# LDM_SCH.net
KiCad netlist of a schematic drawn in Altium Designer
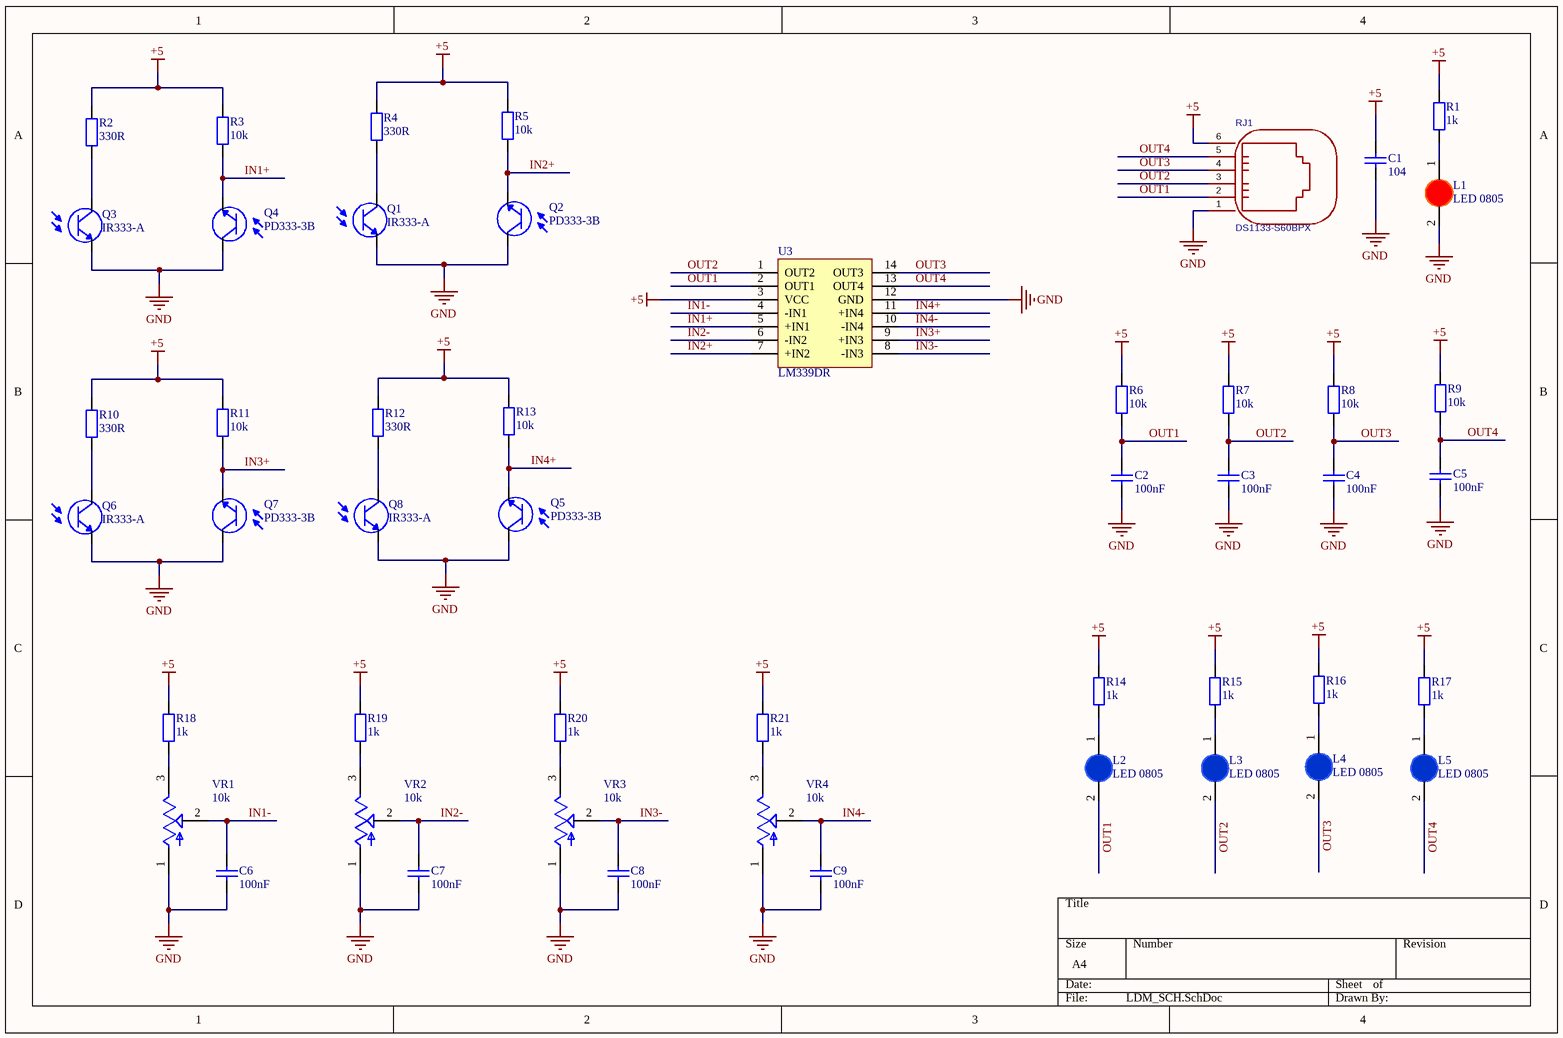
[diagram p0: LDM_SCH.SchDoc]

(export (version "E")
  (design (tool "Eeschema 10.0.6"))
  (components
    (comp (ref "C1")
      (value "104")
      (footprint "tu 0603")
      (description "Dán")
      (libsource (lib "namnt_Lib") (part "Tu 0603 104 50V 10%"))
    )
    (comp (ref "C2")
      (value "100nF")
      (footprint "tu 0603")
      (description "Dán")
      (libsource (lib "namnt_Lib") (part "Tu 0603 104 50V 10%"))
    )
    (comp (ref "C3")
      (value "100nF")
      (footprint "tu 0603")
      (description "Dán")
      (libsource (lib "namnt_Lib") (part "Tu 0603 104 50V 10%"))
    )
    (comp (ref "C4")
      (value "100nF")
      (footprint "tu 0603")
      (description "Dán")
      (libsource (lib "namnt_Lib") (part "Tu 0603 104 50V 10%"))
    )
    (comp (ref "C5")
      (value "100nF")
      (footprint "tu 0603")
      (description "Dán")
      (libsource (lib "namnt_Lib") (part "Tu 0603 104 50V 10%"))
    )
    (comp (ref "C6")
      (value "100nF")
      (footprint "tu 0603")
      (description "Dán")
      (libsource (lib "namnt_Lib") (part "Tu 0603 104 50V 10%"))
    )
    (comp (ref "C7")
      (value "100nF")
      (footprint "tu 0603")
      (description "Dán")
      (libsource (lib "namnt_Lib") (part "Tu 0603 104 50V 10%"))
    )
    (comp (ref "C8")
      (value "100nF")
      (footprint "tu 0603")
      (description "Dán")
      (libsource (lib "namnt_Lib") (part "Tu 0603 104 50V 10%"))
    )
    (comp (ref "C9")
      (value "100nF")
      (footprint "tu 0603")
      (description "Dán")
      (libsource (lib "namnt_Lib") (part "Tu 0603 104 50V 10%"))
    )
    (comp (ref "L1")
      (value "LED 0805")
      (footprint "LED-0805-Red")
      (description "Dán")
      (libsource (lib "namnt_Lib") (part "LED 0805 Do"))
    )
    (comp (ref "L2")
      (value "LED 0805")
      (footprint "LED-0805-Blue")
      (description "Dán")
      (libsource (lib "namnt_Lib") (part "LED 0805 Xanh Duong"))
    )
    (comp (ref "L3")
      (value "LED 0805")
      (footprint "LED-0805-Blue")
      (description "Dán")
      (libsource (lib "namnt_Lib") (part "LED 0805 Xanh Duong"))
    )
    (comp (ref "L4")
      (value "LED 0805")
      (footprint "LED-0805-Blue")
      (description "Dán")
      (libsource (lib "namnt_Lib") (part "LED 0805 Xanh Duong"))
    )
    (comp (ref "L5")
      (value "LED 0805")
      (footprint "LED-0805-Blue")
      (description "Dán")
      (libsource (lib "namnt_Lib") (part "LED 0805 Xanh Duong"))
    )
    (comp (ref "Q1")
      (value "IR333-A")
      (footprint "IR333-A")
      (fields (field (name "MP") "BPW16N"))
      (libsource (lib "namnt_Lib") (part "IR333-A"))
    )
    (comp (ref "Q2")
      (value "PD333-3B")
      (footprint "PD333-3B")
      (fields (field (name "MP") "BPW16N"))
      (libsource (lib "namnt_Lib") (part "PD333-3B"))
    )
    (comp (ref "Q3")
      (value "IR333-A")
      (footprint "IR333-A")
      (fields (field (name "MP") "BPW16N"))
      (libsource (lib "namnt_Lib") (part "IR333-A"))
    )
    (comp (ref "Q4")
      (value "PD333-3B")
      (footprint "PD333-3B")
      (fields (field (name "MP") "BPW16N"))
      (libsource (lib "namnt_Lib") (part "PD333-3B"))
    )
    (comp (ref "Q5")
      (value "PD333-3B")
      (footprint "PD333-3B")
      (fields (field (name "MP") "BPW16N"))
      (libsource (lib "namnt_Lib") (part "PD333-3B"))
    )
    (comp (ref "Q6")
      (value "IR333-A")
      (footprint "IR333-A")
      (fields (field (name "MP") "BPW16N"))
      (libsource (lib "namnt_Lib") (part "IR333-A"))
    )
    (comp (ref "Q7")
      (value "PD333-3B")
      (footprint "PD333-3B")
      (fields (field (name "MP") "BPW16N"))
      (libsource (lib "namnt_Lib") (part "PD333-3B"))
    )
    (comp (ref "Q8")
      (value "IR333-A")
      (footprint "IR333-A")
      (fields (field (name "MP") "BPW16N"))
      (libsource (lib "namnt_Lib") (part "IR333-A"))
    )
    (comp (ref "R1")
      (value "1k")
      (footprint "tro smd 0603")
      (description "Dán")
      (libsource (lib "namnt_Lib") (part "Tro 0603 1% 1k"))
    )
    (comp (ref "R2")
      (value "330R")
      (footprint "tro smd 0603")
      (description "Dán")
      (libsource (lib "namnt_Lib") (part "Tro 0603 5% 330R"))
    )
    (comp (ref "R3")
      (value "10k")
      (footprint "tro smd 0603")
      (description "Dán")
      (libsource (lib "namnt_Lib") (part "Tro 0603 1% 10k"))
    )
    (comp (ref "R4")
      (value "330R")
      (footprint "tro smd 0603")
      (description "Dán")
      (libsource (lib "namnt_Lib") (part "Tro 0603 5% 330R"))
    )
    (comp (ref "R5")
      (value "10k")
      (footprint "tro smd 0603")
      (description "Dán")
      (libsource (lib "namnt_Lib") (part "Tro 0603 1% 10k"))
    )
    (comp (ref "R6")
      (value "10k")
      (footprint "tro smd 0603")
      (description "Dán")
      (libsource (lib "namnt_Lib") (part "Tro 0603 1% 1k"))
    )
    (comp (ref "R7")
      (value "10k")
      (footprint "tro smd 0603")
      (description "Dán")
      (libsource (lib "namnt_Lib") (part "Tro 0603 1% 1k"))
    )
    (comp (ref "R8")
      (value "10k")
      (footprint "tro smd 0603")
      (description "Dán")
      (libsource (lib "namnt_Lib") (part "Tro 0603 1% 1k"))
    )
    (comp (ref "R9")
      (value "10k")
      (footprint "tro smd 0603")
      (description "Dán")
      (libsource (lib "namnt_Lib") (part "Tro 0603 1% 1k"))
    )
    (comp (ref "R10")
      (value "330R")
      (footprint "tro smd 0603")
      (description "Dán")
      (libsource (lib "namnt_Lib") (part "Tro 0603 5% 330R"))
    )
    (comp (ref "R11")
      (value "10k")
      (footprint "tro smd 0603")
      (description "Dán")
      (libsource (lib "namnt_Lib") (part "Tro 0603 1% 10k"))
    )
    (comp (ref "R12")
      (value "330R")
      (footprint "tro smd 0603")
      (description "Dán")
      (libsource (lib "namnt_Lib") (part "Tro 0603 5% 330R"))
    )
    (comp (ref "R13")
      (value "10k")
      (footprint "tro smd 0603")
      (description "Dán")
      (libsource (lib "namnt_Lib") (part "Tro 0603 1% 10k"))
    )
    (comp (ref "R14")
      (value "1k")
      (footprint "tro smd 0603")
      (description "Dán")
      (libsource (lib "namnt_Lib") (part "Tro 0603 1% 1k"))
    )
    (comp (ref "R15")
      (value "1k")
      (footprint "tro smd 0603")
      (description "Dán")
      (libsource (lib "namnt_Lib") (part "Tro 0603 1% 1k"))
    )
    (comp (ref "R16")
      (value "1k")
      (footprint "tro smd 0603")
      (description "Dán")
      (libsource (lib "namnt_Lib") (part "Tro 0603 1% 1k"))
    )
    (comp (ref "R17")
      (value "1k")
      (footprint "tro smd 0603")
      (description "Dán")
      (libsource (lib "namnt_Lib") (part "Tro 0603 1% 1k"))
    )
    (comp (ref "R18")
      (value "1k")
      (footprint "tro smd 0603")
      (description "Dán")
      (libsource (lib "namnt_Lib") (part "Tro 0603 1% 10k"))
    )
    (comp (ref "R19")
      (value "1k")
      (footprint "tro smd 0603")
      (description "Dán")
      (libsource (lib "namnt_Lib") (part "Tro 0603 1% 10k"))
    )
    (comp (ref "R20")
      (value "1k")
      (footprint "tro smd 0603")
      (description "Dán")
      (libsource (lib "namnt_Lib") (part "Tro 0603 1% 10k"))
    )
    (comp (ref "R21")
      (value "1k")
      (footprint "tro smd 0603")
      (description "Dán")
      (libsource (lib "namnt_Lib") (part "Tro 0603 1% 10k"))
    )
    (comp (ref "RJ1")
      (value "DS1133-S60BPX")
      (footprint "RJ11-TH_DS1133-S60BPX")
      (fields (field (name "MANUFACTURER") "CONNFLY"))
      (libsource (lib "namnt_Lib") (part "DS1133-S60BPX"))
    )
    (comp (ref "U3")
      (value "LM339DR")
      (footprint "TSSOP14_25.6_296_15X55_SMD")
      (description "Comparator Differential CMOS, MOS, Open-Collector, TTL 14-SOIC")
      (fields (field (name "MANUFACTURER") "TI National Semiconductor"))
      (libsource (lib "namnt_Lib") (part "IC_LM339DR"))
    )
    (comp (ref "VR1")
      (value "10k")
      (footprint "TRIM_3362P-1-102")
      (description "TRIMMER - 1/4in SQ ST CERMET ¦ Bourns 3362P-1-102")
      (fields (field (name "MF") "Bourns") (field (name "MP") "3362P-1-102"))
      (libsource (lib "namnt_Lib") (part "Bien tro vuong"))
    )
    (comp (ref "VR2")
      (value "10k")
      (footprint "TRIM_3362P-1-102")
      (description "TRIMMER - 1/4in SQ ST CERMET ¦ Bourns 3362P-1-102")
      (fields (field (name "MF") "Bourns") (field (name "MP") "3362P-1-102"))
      (libsource (lib "namnt_Lib") (part "Bien tro vuong"))
    )
    (comp (ref "VR3")
      (value "10k")
      (footprint "TRIM_3362P-1-102")
      (description "TRIMMER - 1/4in SQ ST CERMET ¦ Bourns 3362P-1-102")
      (fields (field (name "MF") "Bourns") (field (name "MP") "3362P-1-102"))
      (libsource (lib "namnt_Lib") (part "Bien tro vuong"))
    )
    (comp (ref "VR4")
      (value "10k")
      (footprint "TRIM_3362P-1-102")
      (description "TRIMMER - 1/4in SQ ST CERMET ¦ Bourns 3362P-1-102")
      (fields (field (name "MF") "Bourns") (field (name "MP") "3362P-1-102"))
      (libsource (lib "namnt_Lib") (part "Bien tro vuong"))
    )
  )
  (nets
    (net (code "1") (name "+5") (class "Default")
      (node (ref "C1") (pin "1") (pinfunction "1_1") (pintype "passive"))
      (node (ref "R1") (pin "2") (pinfunction "2_2") (pintype "passive"))
      (node (ref "R10") (pin "2") (pinfunction "2_2") (pintype "passive"))
      (node (ref "R11") (pin "2") (pinfunction "2_2") (pintype "passive"))
      (node (ref "R12") (pin "2") (pinfunction "2_2") (pintype "passive"))
      (node (ref "R13") (pin "2") (pinfunction "2_2") (pintype "passive"))
      (node (ref "R14") (pin "2") (pinfunction "2_2") (pintype "passive"))
      (node (ref "R15") (pin "2") (pinfunction "2_2") (pintype "passive"))
      (node (ref "R16") (pin "2") (pinfunction "2_2") (pintype "passive"))
      (node (ref "R17") (pin "2") (pinfunction "2_2") (pintype "passive"))
      (node (ref "R18") (pin "2") (pinfunction "2_2") (pintype "passive"))
      (node (ref "R19") (pin "2") (pinfunction "2_2") (pintype "passive"))
      (node (ref "R2") (pin "2") (pinfunction "2_2") (pintype "passive"))
      (node (ref "R20") (pin "2") (pinfunction "2_2") (pintype "passive"))
      (node (ref "R21") (pin "2") (pinfunction "2_2") (pintype "passive"))
      (node (ref "R3") (pin "2") (pinfunction "2_2") (pintype "passive"))
      (node (ref "R4") (pin "2") (pinfunction "2_2") (pintype "passive"))
      (node (ref "R5") (pin "2") (pinfunction "2_2") (pintype "passive"))
      (node (ref "R6") (pin "2") (pinfunction "2_2") (pintype "passive"))
      (node (ref "R7") (pin "2") (pinfunction "2_2") (pintype "passive"))
      (node (ref "R8") (pin "2") (pinfunction "2_2") (pintype "passive"))
      (node (ref "R9") (pin "2") (pinfunction "2_2") (pintype "passive"))
      (node (ref "RJ1") (pin "6") (pinfunction "6_6") (pintype "passive"))
      (node (ref "U3") (pin "3") (pinfunction "VCC_3") (pintype "passive"))
    )
    (net (code "2") (name "/IN1+") (class "Default")
      (node (ref "Q4") (pin "E") (pinfunction "E_E") (pintype "passive"))
      (node (ref "R3") (pin "1") (pinfunction "1_1") (pintype "passive"))
      (node (ref "U3") (pin "5") (pinfunction "+IN1_5") (pintype "passive"))
    )
    (net (code "3") (name "/IN1-") (class "Default")
      (node (ref "C6") (pin "1") (pinfunction "1_1") (pintype "passive"))
      (node (ref "U3") (pin "4") (pinfunction "-IN1_4") (pintype "passive"))
      (node (ref "VR1") (pin "2") (pinfunction "WIPER_2") (pintype "passive"))
    )
    (net (code "4") (name "/IN2+") (class "Default")
      (node (ref "Q2") (pin "E") (pinfunction "E_E") (pintype "passive"))
      (node (ref "R5") (pin "1") (pinfunction "1_1") (pintype "passive"))
      (node (ref "U3") (pin "7") (pinfunction "+IN2_7") (pintype "passive"))
    )
    (net (code "5") (name "/IN2-") (class "Default")
      (node (ref "C7") (pin "1") (pinfunction "1_1") (pintype "passive"))
      (node (ref "U3") (pin "6") (pinfunction "-IN2_6") (pintype "passive"))
      (node (ref "VR2") (pin "2") (pinfunction "WIPER_2") (pintype "passive"))
    )
    (net (code "6") (name "/IN3+") (class "Default")
      (node (ref "Q7") (pin "E") (pinfunction "E_E") (pintype "passive"))
      (node (ref "R11") (pin "1") (pinfunction "1_1") (pintype "passive"))
      (node (ref "U3") (pin "9") (pinfunction "+IN3_9") (pintype "passive"))
    )
    (net (code "7") (name "/IN3-") (class "Default")
      (node (ref "C8") (pin "1") (pinfunction "1_1") (pintype "passive"))
      (node (ref "U3") (pin "8") (pinfunction "-IN3_8") (pintype "passive"))
      (node (ref "VR3") (pin "2") (pinfunction "WIPER_2") (pintype "passive"))
    )
    (net (code "8") (name "/IN4+") (class "Default")
      (node (ref "Q5") (pin "E") (pinfunction "E_E") (pintype "passive"))
      (node (ref "R13") (pin "1") (pinfunction "1_1") (pintype "passive"))
      (node (ref "U3") (pin "11") (pinfunction "+IN4_11") (pintype "passive"))
    )
    (net (code "9") (name "/IN4-") (class "Default")
      (node (ref "C9") (pin "1") (pinfunction "1_1") (pintype "passive"))
      (node (ref "U3") (pin "10") (pinfunction "-IN4_10") (pintype "passive"))
      (node (ref "VR4") (pin "2") (pinfunction "WIPER_2") (pintype "passive"))
    )
    (net (code "10") (name "/OUT1") (class "Default")
      (node (ref "C2") (pin "1") (pinfunction "1_1") (pintype "passive"))
      (node (ref "L2") (pin "2") (pinfunction "K_2") (pintype "passive"))
      (node (ref "R6") (pin "1") (pinfunction "1_1") (pintype "passive"))
      (node (ref "RJ1") (pin "2") (pinfunction "2_2") (pintype "passive"))
      (node (ref "U3") (pin "2") (pinfunction "OUT1_2") (pintype "passive"))
    )
    (net (code "11") (name "/OUT2") (class "Default")
      (node (ref "C3") (pin "1") (pinfunction "1_1") (pintype "passive"))
      (node (ref "L3") (pin "2") (pinfunction "K_2") (pintype "passive"))
      (node (ref "R7") (pin "1") (pinfunction "1_1") (pintype "passive"))
      (node (ref "RJ1") (pin "3") (pinfunction "3_3") (pintype "passive"))
      (node (ref "U3") (pin "1") (pinfunction "OUT2_1") (pintype "passive"))
    )
    (net (code "12") (name "/OUT3") (class "Default")
      (node (ref "C4") (pin "1") (pinfunction "1_1") (pintype "passive"))
      (node (ref "L4") (pin "2") (pinfunction "K_2") (pintype "passive"))
      (node (ref "R8") (pin "1") (pinfunction "1_1") (pintype "passive"))
      (node (ref "RJ1") (pin "4") (pinfunction "4_4") (pintype "passive"))
      (node (ref "U3") (pin "14") (pinfunction "OUT3_14") (pintype "passive"))
    )
    (net (code "13") (name "/OUT4") (class "Default")
      (node (ref "C5") (pin "1") (pinfunction "1_1") (pintype "passive"))
      (node (ref "L5") (pin "2") (pinfunction "K_2") (pintype "passive"))
      (node (ref "R9") (pin "1") (pinfunction "1_1") (pintype "passive"))
      (node (ref "RJ1") (pin "5") (pinfunction "5_5") (pintype "passive"))
      (node (ref "U3") (pin "13") (pinfunction "OUT4_13") (pintype "passive"))
    )
    (net (code "14") (name "GND") (class "Default")
      (node (ref "C1") (pin "2") (pinfunction "2_2") (pintype "passive"))
      (node (ref "C2") (pin "2") (pinfunction "2_2") (pintype "passive"))
      (node (ref "C3") (pin "2") (pinfunction "2_2") (pintype "passive"))
      (node (ref "C4") (pin "2") (pinfunction "2_2") (pintype "passive"))
      (node (ref "C5") (pin "2") (pinfunction "2_2") (pintype "passive"))
      (node (ref "C6") (pin "2") (pinfunction "2_2") (pintype "passive"))
      (node (ref "C7") (pin "2") (pinfunction "2_2") (pintype "passive"))
      (node (ref "C8") (pin "2") (pinfunction "2_2") (pintype "passive"))
      (node (ref "C9") (pin "2") (pinfunction "2_2") (pintype "passive"))
      (node (ref "L1") (pin "2") (pinfunction "K_2") (pintype "passive"))
      (node (ref "Q1") (pin "E") (pinfunction "E_E") (pintype "passive"))
      (node (ref "Q2") (pin "C") (pinfunction "C_C") (pintype "passive"))
      (node (ref "Q3") (pin "E") (pinfunction "E_E") (pintype "passive"))
      (node (ref "Q4") (pin "C") (pinfunction "C_C") (pintype "passive"))
      (node (ref "Q5") (pin "C") (pinfunction "C_C") (pintype "passive"))
      (node (ref "Q6") (pin "E") (pinfunction "E_E") (pintype "passive"))
      (node (ref "Q7") (pin "C") (pinfunction "C_C") (pintype "passive"))
      (node (ref "Q8") (pin "E") (pinfunction "E_E") (pintype "passive"))
      (node (ref "RJ1") (pin "1") (pinfunction "1_1") (pintype "passive"))
      (node (ref "U3") (pin "12") (pinfunction "GND_12") (pintype "passive"))
      (node (ref "VR1") (pin "1") (pinfunction "CCW_1") (pintype "passive"))
      (node (ref "VR2") (pin "1") (pinfunction "CCW_1") (pintype "passive"))
      (node (ref "VR3") (pin "1") (pinfunction "CCW_1") (pintype "passive"))
      (node (ref "VR4") (pin "1") (pinfunction "CCW_1") (pintype "passive"))
    )
    (net (code "15") (name "Net-(L1-A)") (class "Default")
      (node (ref "L1") (pin "1") (pinfunction "A_1") (pintype "passive"))
      (node (ref "R1") (pin "1") (pinfunction "1_1") (pintype "passive"))
    )
    (net (code "16") (name "Net-(L2-A)") (class "Default")
      (node (ref "L2") (pin "1") (pinfunction "A_1") (pintype "passive"))
      (node (ref "R14") (pin "1") (pinfunction "1_1") (pintype "passive"))
    )
    (net (code "17") (name "Net-(L3-A)") (class "Default")
      (node (ref "L3") (pin "1") (pinfunction "A_1") (pintype "passive"))
      (node (ref "R15") (pin "1") (pinfunction "1_1") (pintype "passive"))
    )
    (net (code "18") (name "Net-(L4-A)") (class "Default")
      (node (ref "L4") (pin "1") (pinfunction "A_1") (pintype "passive"))
      (node (ref "R16") (pin "1") (pinfunction "1_1") (pintype "passive"))
    )
    (net (code "19") (name "Net-(L5-A)") (class "Default")
      (node (ref "L5") (pin "1") (pinfunction "A_1") (pintype "passive"))
      (node (ref "R17") (pin "1") (pinfunction "1_1") (pintype "passive"))
    )
    (net (code "20") (name "Net-(Q1-PadC)") (class "Default")
      (node (ref "Q1") (pin "C") (pinfunction "C_C") (pintype "passive"))
      (node (ref "R4") (pin "1") (pinfunction "1_1") (pintype "passive"))
    )
    (net (code "21") (name "Net-(Q3-PadC)") (class "Default")
      (node (ref "Q3") (pin "C") (pinfunction "C_C") (pintype "passive"))
      (node (ref "R2") (pin "1") (pinfunction "1_1") (pintype "passive"))
    )
    (net (code "22") (name "Net-(Q6-PadC)") (class "Default")
      (node (ref "Q6") (pin "C") (pinfunction "C_C") (pintype "passive"))
      (node (ref "R10") (pin "1") (pinfunction "1_1") (pintype "passive"))
    )
    (net (code "23") (name "Net-(Q8-PadC)") (class "Default")
      (node (ref "Q8") (pin "C") (pinfunction "C_C") (pintype "passive"))
      (node (ref "R12") (pin "1") (pinfunction "1_1") (pintype "passive"))
    )
    (net (code "24") (name "Net-(VR1-CW)") (class "Default")
      (node (ref "R18") (pin "1") (pinfunction "1_1") (pintype "passive"))
      (node (ref "VR1") (pin "3") (pinfunction "CW_3") (pintype "passive"))
    )
    (net (code "25") (name "Net-(VR2-CW)") (class "Default")
      (node (ref "R19") (pin "1") (pinfunction "1_1") (pintype "passive"))
      (node (ref "VR2") (pin "3") (pinfunction "CW_3") (pintype "passive"))
    )
    (net (code "26") (name "Net-(VR3-CW)") (class "Default")
      (node (ref "R20") (pin "1") (pinfunction "1_1") (pintype "passive"))
      (node (ref "VR3") (pin "3") (pinfunction "CW_3") (pintype "passive"))
    )
    (net (code "27") (name "Net-(VR4-CW)") (class "Default")
      (node (ref "R21") (pin "1") (pinfunction "1_1") (pintype "passive"))
      (node (ref "VR4") (pin "3") (pinfunction "CW_3") (pintype "passive"))
    )
  )
)
